# Ethernet1_Power.net
KiCad netlist of a schematic drawn in Altium Designer
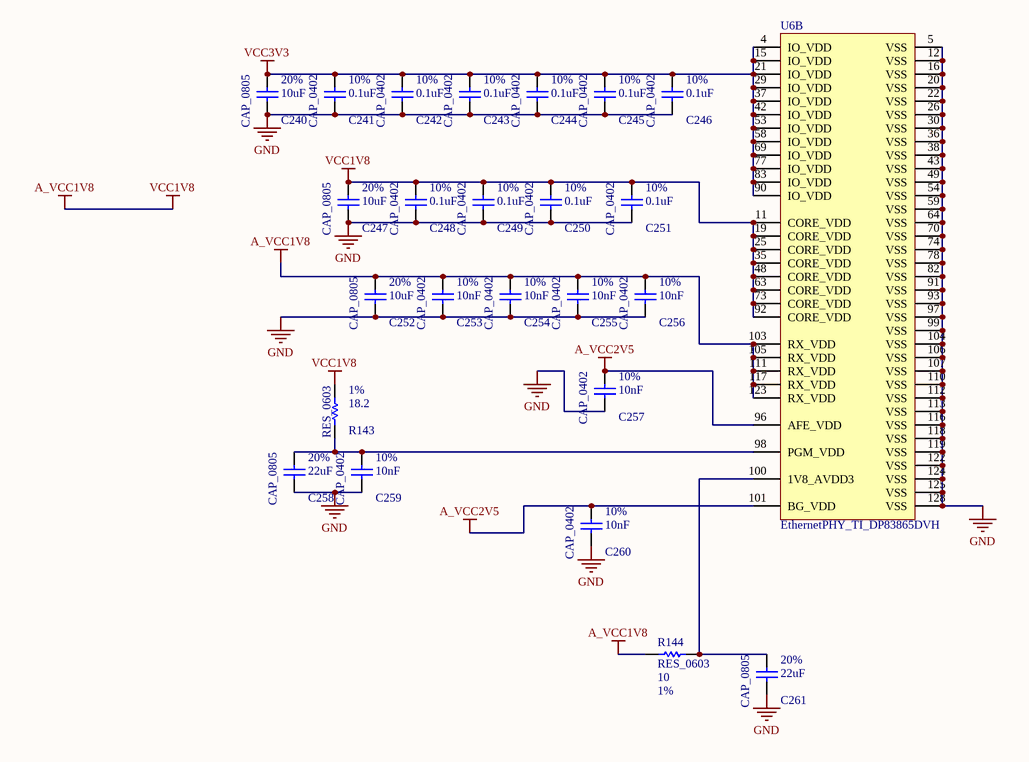
[diagram p0: Ethernet1_Power.SchDoc]

(export (version "E")
  (design (tool "Eeschema 10.0.6"))
  (components
    (comp (ref "C240")
      (value "CAP_0805")
      (footprint "CAPC0805(2012)75_N")
      (description "10uF, ceramic, 20%, 6.3V, X5R 0805")
      (fields
        (field (name "ALTIUM_VALUE") "10uF")
        (field (name "TOLERANCE") "20%")
        (field (name "PART NUMBER") "ECJ-2FB0J106M")
        (field (name "MANUFACTURER") "Panasonic - ECG")
      )
      (libsource (lib "COMRAD_Database") (part "CAP_0805"))
    )
    (comp (ref "C241")
      (value "CAP_0402")
      (footprint "CAPC0402(1005)60_N:CAPC0402(1005)60_N")
      (description "0.1uf, ceramic, 10%, 6.3V, X5R, 0402")
      (fields
        (field (name "ALTIUM_VALUE") "0.1uF")
        (field (name "TOLERANCE") "10%")
        (field (name "PART NUMBER") "C1005X5R0J104K")
        (field (name "MANUFACTURER") "TDK Corporation")
      )
      (libsource (lib "COMRAD_Database") (part "CAP_0402"))
    )
    (comp (ref "C242")
      (value "CAP_0402")
      (footprint "CAPC0402(1005)60_N:CAPC0402(1005)60_N")
      (description "0.1uf, ceramic, 10%, 6.3V, X5R, 0402")
      (fields
        (field (name "ALTIUM_VALUE") "0.1uF")
        (field (name "TOLERANCE") "10%")
        (field (name "PART NUMBER") "C1005X5R0J104K")
        (field (name "MANUFACTURER") "TDK Corporation")
      )
      (libsource (lib "COMRAD_Database") (part "CAP_0402"))
    )
    (comp (ref "C243")
      (value "CAP_0402")
      (footprint "CAPC0402(1005)60_N:CAPC0402(1005)60_N")
      (description "0.1uf, ceramic, 10%, 6.3V, X5R, 0402")
      (fields
        (field (name "ALTIUM_VALUE") "0.1uF")
        (field (name "TOLERANCE") "10%")
        (field (name "PART NUMBER") "C1005X5R0J104K")
        (field (name "MANUFACTURER") "TDK Corporation")
      )
      (libsource (lib "COMRAD_Database") (part "CAP_0402"))
    )
    (comp (ref "C244")
      (value "CAP_0402")
      (footprint "CAPC0402(1005)60_N:CAPC0402(1005)60_N")
      (description "0.1uf, ceramic, 10%, 6.3V, X5R, 0402")
      (fields
        (field (name "ALTIUM_VALUE") "0.1uF")
        (field (name "TOLERANCE") "10%")
        (field (name "PART NUMBER") "C1005X5R0J104K")
        (field (name "MANUFACTURER") "TDK Corporation")
      )
      (libsource (lib "COMRAD_Database") (part "CAP_0402"))
    )
    (comp (ref "C245")
      (value "CAP_0402")
      (footprint "CAPC0402(1005)60_N:CAPC0402(1005)60_N")
      (description "0.1uf, ceramic, 10%, 6.3V, X5R, 0402")
      (fields
        (field (name "ALTIUM_VALUE") "0.1uF")
        (field (name "TOLERANCE") "10%")
        (field (name "PART NUMBER") "C1005X5R0J104K")
        (field (name "MANUFACTURER") "TDK Corporation")
      )
      (libsource (lib "COMRAD_Database") (part "CAP_0402"))
    )
    (comp (ref "C246")
      (value "CAP_0402")
      (footprint "CAPC0402(1005)60_N:CAPC0402(1005)60_N")
      (description "0.1uf, ceramic, 10%, 6.3V, X5R, 0402")
      (fields
        (field (name "ALTIUM_VALUE") "0.1uF")
        (field (name "TOLERANCE") "10%")
        (field (name "PART NUMBER") "C1005X5R0J104K")
        (field (name "MANUFACTURER") "TDK Corporation")
      )
      (libsource (lib "COMRAD_Database") (part "CAP_0402"))
    )
    (comp (ref "C247")
      (value "CAP_0805")
      (footprint "CAPC0805(2012)75_N")
      (description "10uF, ceramic, 20%, 6.3V, X5R 0805")
      (fields
        (field (name "ALTIUM_VALUE") "10uF")
        (field (name "TOLERANCE") "20%")
        (field (name "PART NUMBER") "ECJ-2FB0J106M")
        (field (name "MANUFACTURER") "Panasonic - ECG")
      )
      (libsource (lib "COMRAD_Database") (part "CAP_0805"))
    )
    (comp (ref "C248")
      (value "CAP_0402")
      (footprint "CAPC0402(1005)60_N:CAPC0402(1005)60_N")
      (description "0.1uf, ceramic, 10%, 6.3V, X5R, 0402")
      (fields
        (field (name "ALTIUM_VALUE") "0.1uF")
        (field (name "TOLERANCE") "10%")
        (field (name "PART NUMBER") "C1005X5R0J104K")
        (field (name "MANUFACTURER") "TDK Corporation")
      )
      (libsource (lib "COMRAD_Database") (part "CAP_0402"))
    )
    (comp (ref "C249")
      (value "CAP_0402")
      (footprint "CAPC0402(1005)60_N:CAPC0402(1005)60_N")
      (description "0.1uf, ceramic, 10%, 6.3V, X5R, 0402")
      (fields
        (field (name "ALTIUM_VALUE") "0.1uF")
        (field (name "TOLERANCE") "10%")
        (field (name "PART NUMBER") "C1005X5R0J104K")
        (field (name "MANUFACTURER") "TDK Corporation")
      )
      (libsource (lib "COMRAD_Database") (part "CAP_0402"))
    )
    (comp (ref "C250")
      (value "CAP_0402")
      (footprint "CAPC0402(1005)60_N:CAPC0402(1005)60_N")
      (description "0.1uf, ceramic, 10%, 6.3V, X5R, 0402")
      (fields
        (field (name "ALTIUM_VALUE") "0.1uF")
        (field (name "TOLERANCE") "10%")
        (field (name "PART NUMBER") "C1005X5R0J104K")
        (field (name "MANUFACTURER") "TDK Corporation")
      )
      (libsource (lib "COMRAD_Database") (part "CAP_0402"))
    )
    (comp (ref "C251")
      (value "CAP_0402")
      (footprint "CAPC0402(1005)60_N:CAPC0402(1005)60_N")
      (description "0.1uf, ceramic, 10%, 6.3V, X5R, 0402")
      (fields
        (field (name "ALTIUM_VALUE") "0.1uF")
        (field (name "TOLERANCE") "10%")
        (field (name "PART NUMBER") "C1005X5R0J104K")
        (field (name "MANUFACTURER") "TDK Corporation")
      )
      (libsource (lib "COMRAD_Database") (part "CAP_0402"))
    )
    (comp (ref "C252")
      (value "CAP_0805")
      (footprint "CAPC0805(2012)75_N")
      (description "10uF, ceramic, 20%, 6.3V, X5R 0805")
      (fields
        (field (name "ALTIUM_VALUE") "10uF")
        (field (name "TOLERANCE") "20%")
        (field (name "PART NUMBER") "ECJ-2FB0J106M")
        (field (name "MANUFACTURER") "Panasonic - ECG")
      )
      (libsource (lib "COMRAD_Database") (part "CAP_0805"))
    )
    (comp (ref "C253")
      (value "CAP_0402")
      (footprint "CAPC0402(1005)60_N:CAPC0402(1005)60_N")
      (description "10000pF, ceramic, 10% 6.3V X5R, 0402")
      (fields
        (field (name "ALTIUM_VALUE") "10nF")
        (field (name "TOLERANCE") "10%")
        (field (name "PART NUMBER") "GRM155R60J103KA01D")
        (field (name "MANUFACTURER") "Murata Electronics North America")
      )
      (libsource (lib "COMRAD_Database") (part "CAP_0402"))
    )
    (comp (ref "C254")
      (value "CAP_0402")
      (footprint "CAPC0402(1005)60_N:CAPC0402(1005)60_N")
      (description "10000pF, ceramic, 10% 6.3V X5R, 0402")
      (fields
        (field (name "ALTIUM_VALUE") "10nF")
        (field (name "TOLERANCE") "10%")
        (field (name "PART NUMBER") "GRM155R60J103KA01D")
        (field (name "MANUFACTURER") "Murata Electronics North America")
      )
      (libsource (lib "COMRAD_Database") (part "CAP_0402"))
    )
    (comp (ref "C255")
      (value "CAP_0402")
      (footprint "CAPC0402(1005)60_N:CAPC0402(1005)60_N")
      (description "10000pF, ceramic, 10% 6.3V X5R, 0402")
      (fields
        (field (name "ALTIUM_VALUE") "10nF")
        (field (name "TOLERANCE") "10%")
        (field (name "PART NUMBER") "GRM155R60J103KA01D")
        (field (name "MANUFACTURER") "Murata Electronics North America")
      )
      (libsource (lib "COMRAD_Database") (part "CAP_0402"))
    )
    (comp (ref "C256")
      (value "CAP_0402")
      (footprint "CAPC0402(1005)60_N:CAPC0402(1005)60_N")
      (description "10000pF, ceramic, 10% 6.3V X5R, 0402")
      (fields
        (field (name "ALTIUM_VALUE") "10nF")
        (field (name "TOLERANCE") "10%")
        (field (name "PART NUMBER") "GRM155R60J103KA01D")
        (field (name "MANUFACTURER") "Murata Electronics North America")
      )
      (libsource (lib "COMRAD_Database") (part "CAP_0402"))
    )
    (comp (ref "C257")
      (value "CAP_0402")
      (footprint "CAPC0402(1005)60_N:CAPC0402(1005)60_N")
      (description "10000pF, ceramic, 10% 6.3V X5R, 0402")
      (fields
        (field (name "ALTIUM_VALUE") "10nF")
        (field (name "TOLERANCE") "10%")
        (field (name "PART NUMBER") "GRM155R60J103KA01D")
        (field (name "MANUFACTURER") "Murata Electronics North America")
      )
      (libsource (lib "COMRAD_Database") (part "CAP_0402"))
    )
    (comp (ref "C258")
      (value "CAP_0805")
      (footprint "CAPC0805(2012)75_N")
      (description "22uF, ceramic, 20%, 6.3V, X5R, 0805")
      (fields
        (field (name "ALTIUM_VALUE") "22uF")
        (field (name "TOLERANCE") "20%")
        (field (name "PART NUMBER") "JMK212BJ226MG-T")
        (field (name "MANUFACTURER") "Taiyo Yuden")
      )
      (libsource (lib "COMRAD_Database") (part "CAP_0805"))
    )
    (comp (ref "C259")
      (value "CAP_0402")
      (footprint "CAPC0402(1005)60_N:CAPC0402(1005)60_N")
      (description "10000pF, ceramic, 10% 6.3V X5R, 0402")
      (fields
        (field (name "ALTIUM_VALUE") "10nF")
        (field (name "TOLERANCE") "10%")
        (field (name "PART NUMBER") "GRM155R60J103KA01D")
        (field (name "MANUFACTURER") "Murata Electronics North America")
      )
      (libsource (lib "COMRAD_Database") (part "CAP_0402"))
    )
    (comp (ref "C260")
      (value "CAP_0402")
      (footprint "CAPC0402(1005)60_N:CAPC0402(1005)60_N")
      (description "10000pF, ceramic, 10% 6.3V X5R, 0402")
      (fields
        (field (name "ALTIUM_VALUE") "10nF")
        (field (name "TOLERANCE") "10%")
        (field (name "PART NUMBER") "GRM155R60J103KA01D")
        (field (name "MANUFACTURER") "Murata Electronics North America")
      )
      (libsource (lib "COMRAD_Database") (part "CAP_0402"))
    )
    (comp (ref "C261")
      (value "CAP_0805")
      (footprint "CAPC0805(2012)75_N")
      (description "22uF, ceramic, 20%, 6.3V, X5R, 0805")
      (fields
        (field (name "ALTIUM_VALUE") "22uF")
        (field (name "TOLERANCE") "20%")
        (field (name "PART NUMBER") "JMK212BJ226MG-T")
        (field (name "MANUFACTURER") "Taiyo Yuden")
      )
      (libsource (lib "COMRAD_Database") (part "CAP_0805"))
    )
    (comp (ref "R143")
      (value "RES_0603")
      (footprint "RESC0603(1608)_N")
      (description "RES 18.2 OHM 1/10W 1% 0603 SMD")
      (fields
        (field (name "ALTIUM_VALUE") "18.2")
        (field (name "TOLERANCE") "1%")
        (field (name "PART NUMBER") "ERJ-3EKF18R2V")
        (field (name "MANUFACTURER") "Panasonic Electronics Components")
      )
      (libsource (lib "COMRAD_Database") (part "RES_0603"))
    )
    (comp (ref "R144")
      (value "RES_0603")
      (footprint "RESC0603(1608)_N")
      (description "RES 10.0 OHM 1/10W 1% 0603 SMD")
      (fields
        (field (name "ALTIUM_VALUE") "10")
        (field (name "TOLERANCE") "1%")
        (field (name "PART NUMBER") "ERJ-3EKF10R0V")
        (field (name "MANUFACTURER") "Panasonic Electronics Components")
      )
      (libsource (lib "COMRAD_Database") (part "RES_0603"))
    )
    (comp (ref "U6")
      (value "EthernetPHY_TI_DP83865DVH")
      (footprint "EthernetPHY_TI_DP83865(PQFP)_VLA128A_N")
      (description "Ethernet PHY_TI_DP83865DVH, Gigabit Ethernet PHYTER,128 Lead Plastic Flat Pack")
      (fields (field (name "PART NUMBER") "DP83865DVH") (field (name "MANUFACTURER") "Texas Instruments"))
      (libsource (lib "COMRAD_Database") (part "EthernetPHY_TI_DP83865DVH"))
    )
  )
  (nets
    (net (code "1") (name "A_VCC1V8") (class "Default")
      (node (ref "C247") (pin "2") (pinfunction "2_2") (pintype "passive"))
      (node (ref "C248") (pin "2") (pinfunction "2_2") (pintype "passive"))
      (node (ref "C249") (pin "2") (pinfunction "2_2") (pintype "passive"))
      (node (ref "C250") (pin "2") (pinfunction "2_2") (pintype "passive"))
      (node (ref "C251") (pin "2") (pinfunction "2_2") (pintype "passive"))
      (node (ref "C252") (pin "2") (pinfunction "2_2") (pintype "passive"))
      (node (ref "C253") (pin "2") (pinfunction "2_2") (pintype "passive"))
      (node (ref "C254") (pin "2") (pinfunction "2_2") (pintype "passive"))
      (node (ref "C255") (pin "2") (pinfunction "2_2") (pintype "passive"))
      (node (ref "C256") (pin "2") (pinfunction "2_2") (pintype "passive"))
      (node (ref "R143") (pin "2") (pinfunction "2_2") (pintype "passive"))
      (node (ref "R144") (pin "2") (pinfunction "2_2") (pintype "passive"))
      (node (ref "U6") (pin "103") (pinfunction "RX_VDD_103") (pintype "power_in"))
      (node (ref "U6") (pin "105") (pinfunction "RX_VDD_105") (pintype "power_in"))
      (node (ref "U6") (pin "11") (pinfunction "CORE_VDD_11") (pintype "power_in"))
      (node (ref "U6") (pin "111") (pinfunction "RX_VDD_111") (pintype "power_in"))
      (node (ref "U6") (pin "117") (pinfunction "RX_VDD_117") (pintype "power_in"))
      (node (ref "U6") (pin "123") (pinfunction "RX_VDD_123") (pintype "power_in"))
      (node (ref "U6") (pin "19") (pinfunction "CORE_VDD_19") (pintype "power_in"))
      (node (ref "U6") (pin "25") (pinfunction "CORE_VDD_25") (pintype "power_in"))
      (node (ref "U6") (pin "35") (pinfunction "CORE_VDD_35") (pintype "power_in"))
      (node (ref "U6") (pin "48") (pinfunction "CORE_VDD_48") (pintype "power_in"))
      (node (ref "U6") (pin "63") (pinfunction "CORE_VDD_63") (pintype "power_in"))
      (node (ref "U6") (pin "73") (pinfunction "CORE_VDD_73") (pintype "power_in"))
      (node (ref "U6") (pin "92") (pinfunction "CORE_VDD_92") (pintype "power_in"))
    )
    (net (code "2") (name "A_VCC2V5") (class "Default")
      (node (ref "C257") (pin "2") (pinfunction "2_2") (pintype "passive"))
      (node (ref "C260") (pin "2") (pinfunction "2_2") (pintype "passive"))
      (node (ref "U6") (pin "101") (pinfunction "BG_VDD_101") (pintype "power_in"))
      (node (ref "U6") (pin "96") (pinfunction "AFE_VDD_96") (pintype "power_in"))
    )
    (net (code "3") (name "GND") (class "Default")
      (node (ref "C240") (pin "1") (pinfunction "1_1") (pintype "passive"))
      (node (ref "C241") (pin "1") (pinfunction "1_1") (pintype "passive"))
      (node (ref "C242") (pin "1") (pinfunction "1_1") (pintype "passive"))
      (node (ref "C243") (pin "1") (pinfunction "1_1") (pintype "passive"))
      (node (ref "C244") (pin "1") (pinfunction "1_1") (pintype "passive"))
      (node (ref "C245") (pin "1") (pinfunction "1_1") (pintype "passive"))
      (node (ref "C246") (pin "1") (pinfunction "1_1") (pintype "passive"))
      (node (ref "C247") (pin "1") (pinfunction "1_1") (pintype "passive"))
      (node (ref "C248") (pin "1") (pinfunction "1_1") (pintype "passive"))
      (node (ref "C249") (pin "1") (pinfunction "1_1") (pintype "passive"))
      (node (ref "C250") (pin "1") (pinfunction "1_1") (pintype "passive"))
      (node (ref "C251") (pin "1") (pinfunction "1_1") (pintype "passive"))
      (node (ref "C252") (pin "1") (pinfunction "1_1") (pintype "passive"))
      (node (ref "C253") (pin "1") (pinfunction "1_1") (pintype "passive"))
      (node (ref "C254") (pin "1") (pinfunction "1_1") (pintype "passive"))
      (node (ref "C255") (pin "1") (pinfunction "1_1") (pintype "passive"))
      (node (ref "C256") (pin "1") (pinfunction "1_1") (pintype "passive"))
      (node (ref "C257") (pin "1") (pinfunction "1_1") (pintype "passive"))
      (node (ref "C258") (pin "1") (pinfunction "1_1") (pintype "passive"))
      (node (ref "C259") (pin "1") (pinfunction "1_1") (pintype "passive"))
      (node (ref "C260") (pin "1") (pinfunction "1_1") (pintype "passive"))
      (node (ref "C261") (pin "1") (pinfunction "1_1") (pintype "passive"))
      (node (ref "U6") (pin "104") (pinfunction "VSS_104") (pintype "power_in"))
      (node (ref "U6") (pin "106") (pinfunction "VSS_106") (pintype "power_in"))
      (node (ref "U6") (pin "107") (pinfunction "VSS_107") (pintype "power_in"))
      (node (ref "U6") (pin "110") (pinfunction "VSS_110") (pintype "power_in"))
      (node (ref "U6") (pin "112") (pinfunction "VSS_112") (pintype "power_in"))
      (node (ref "U6") (pin "113") (pinfunction "VSS_113") (pintype "power_in"))
      (node (ref "U6") (pin "116") (pinfunction "VSS_116") (pintype "power_in"))
      (node (ref "U6") (pin "118") (pinfunction "VSS_118") (pintype "power_in"))
      (node (ref "U6") (pin "119") (pinfunction "VSS_119") (pintype "power_in"))
      (node (ref "U6") (pin "12") (pinfunction "VSS_12") (pintype "power_in"))
      (node (ref "U6") (pin "122") (pinfunction "VSS_122") (pintype "power_in"))
      (node (ref "U6") (pin "124") (pinfunction "VSS_124") (pintype "power_in"))
      (node (ref "U6") (pin "125") (pinfunction "VSS_125") (pintype "power_in"))
      (node (ref "U6") (pin "128") (pinfunction "VSS_128") (pintype "power_in"))
      (node (ref "U6") (pin "16") (pinfunction "VSS_16") (pintype "power_in"))
      (node (ref "U6") (pin "20") (pinfunction "VSS_20") (pintype "power_in"))
      (node (ref "U6") (pin "22") (pinfunction "VSS_22") (pintype "power_in"))
      (node (ref "U6") (pin "26") (pinfunction "VSS_26") (pintype "power_in"))
      (node (ref "U6") (pin "30") (pinfunction "VSS_30") (pintype "power_in"))
      (node (ref "U6") (pin "36") (pinfunction "VSS_36") (pintype "power_in"))
      (node (ref "U6") (pin "38") (pinfunction "VSS_38") (pintype "power_in"))
      (node (ref "U6") (pin "43") (pinfunction "VSS_43") (pintype "power_in"))
      (node (ref "U6") (pin "49") (pinfunction "VSS_49") (pintype "power_in"))
      (node (ref "U6") (pin "5") (pinfunction "VSS_5") (pintype "power_in"))
      (node (ref "U6") (pin "54") (pinfunction "VSS_54") (pintype "power_in"))
      (node (ref "U6") (pin "59") (pinfunction "VSS_59") (pintype "power_in"))
      (node (ref "U6") (pin "64") (pinfunction "VSS_64") (pintype "power_in"))
      (node (ref "U6") (pin "70") (pinfunction "VSS_70") (pintype "power_in"))
      (node (ref "U6") (pin "74") (pinfunction "VSS_74") (pintype "power_in"))
      (node (ref "U6") (pin "78") (pinfunction "VSS_78") (pintype "power_in"))
      (node (ref "U6") (pin "82") (pinfunction "VSS_82") (pintype "power_in"))
      (node (ref "U6") (pin "91") (pinfunction "VSS_91") (pintype "power_in"))
      (node (ref "U6") (pin "93") (pinfunction "VSS_93") (pintype "power_in"))
      (node (ref "U6") (pin "97") (pinfunction "VSS_97") (pintype "power_in"))
      (node (ref "U6") (pin "99") (pinfunction "VSS_99") (pintype "power_in"))
    )
    (net (code "4") (name "Net-(U6B-1V8_AVDD3)") (class "Default")
      (node (ref "C261") (pin "2") (pinfunction "2_2") (pintype "passive"))
      (node (ref "R144") (pin "1") (pinfunction "1_1") (pintype "passive"))
      (node (ref "U6") (pin "100") (pinfunction "1V8_AVDD3_100") (pintype "power_in"))
    )
    (net (code "5") (name "Net-(U6B-PGM_VDD)") (class "Default")
      (node (ref "C258") (pin "2") (pinfunction "2_2") (pintype "passive"))
      (node (ref "C259") (pin "2") (pinfunction "2_2") (pintype "passive"))
      (node (ref "R143") (pin "1") (pinfunction "1_1") (pintype "passive"))
      (node (ref "U6") (pin "98") (pinfunction "PGM_VDD_98") (pintype "power_in"))
    )
    (net (code "6") (name "VCC3V3") (class "Default")
      (node (ref "C240") (pin "2") (pinfunction "2_2") (pintype "passive"))
      (node (ref "C241") (pin "2") (pinfunction "2_2") (pintype "passive"))
      (node (ref "C242") (pin "2") (pinfunction "2_2") (pintype "passive"))
      (node (ref "C243") (pin "2") (pinfunction "2_2") (pintype "passive"))
      (node (ref "C244") (pin "2") (pinfunction "2_2") (pintype "passive"))
      (node (ref "C245") (pin "2") (pinfunction "2_2") (pintype "passive"))
      (node (ref "C246") (pin "2") (pinfunction "2_2") (pintype "passive"))
      (node (ref "U6") (pin "15") (pinfunction "IO_VDD_15") (pintype "power_in"))
      (node (ref "U6") (pin "21") (pinfunction "IO_VDD_21") (pintype "power_in"))
      (node (ref "U6") (pin "29") (pinfunction "IO_VDD_29") (pintype "power_in"))
      (node (ref "U6") (pin "37") (pinfunction "IO_VDD_37") (pintype "power_in"))
      (node (ref "U6") (pin "4") (pinfunction "IO_VDD_4") (pintype "power_in"))
      (node (ref "U6") (pin "42") (pinfunction "IO_VDD_42") (pintype "power_in"))
      (node (ref "U6") (pin "53") (pinfunction "IO_VDD_53") (pintype "power_in"))
      (node (ref "U6") (pin "58") (pinfunction "IO_VDD_58") (pintype "power_in"))
      (node (ref "U6") (pin "69") (pinfunction "IO_VDD_69") (pintype "power_in"))
      (node (ref "U6") (pin "77") (pinfunction "IO_VDD_77") (pintype "power_in"))
      (node (ref "U6") (pin "83") (pinfunction "IO_VDD_83") (pintype "power_in"))
      (node (ref "U6") (pin "90") (pinfunction "IO_VDD_90") (pintype "power_in"))
    )
  )
)
